# pandora_B_v1.net
KiCad netlist of a schematic drawn in EAGLE
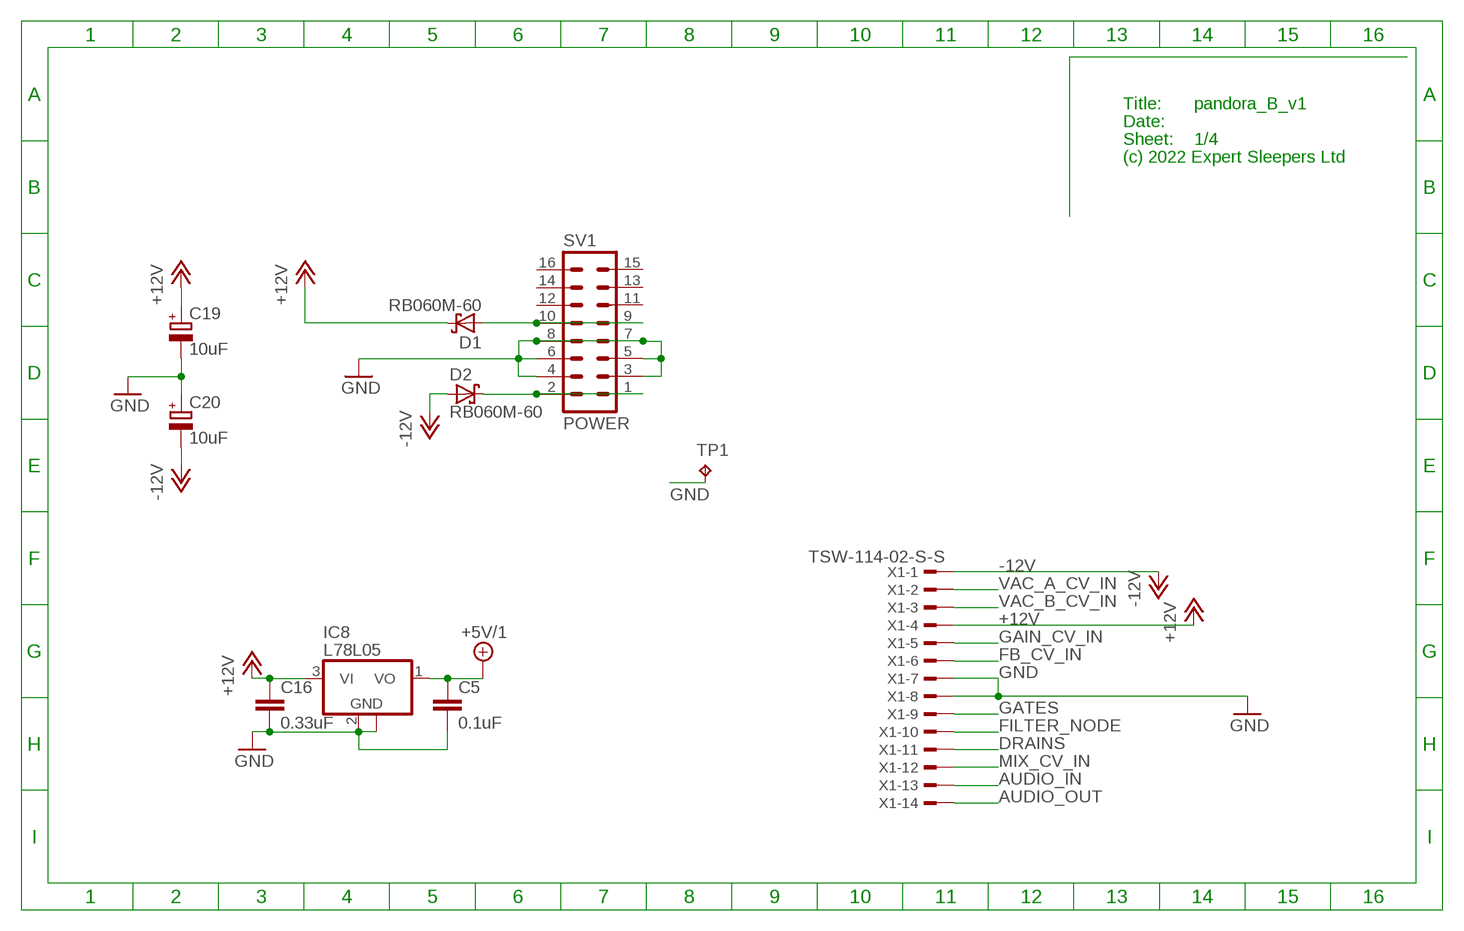
[diagram p0: schematic, sheet 1]
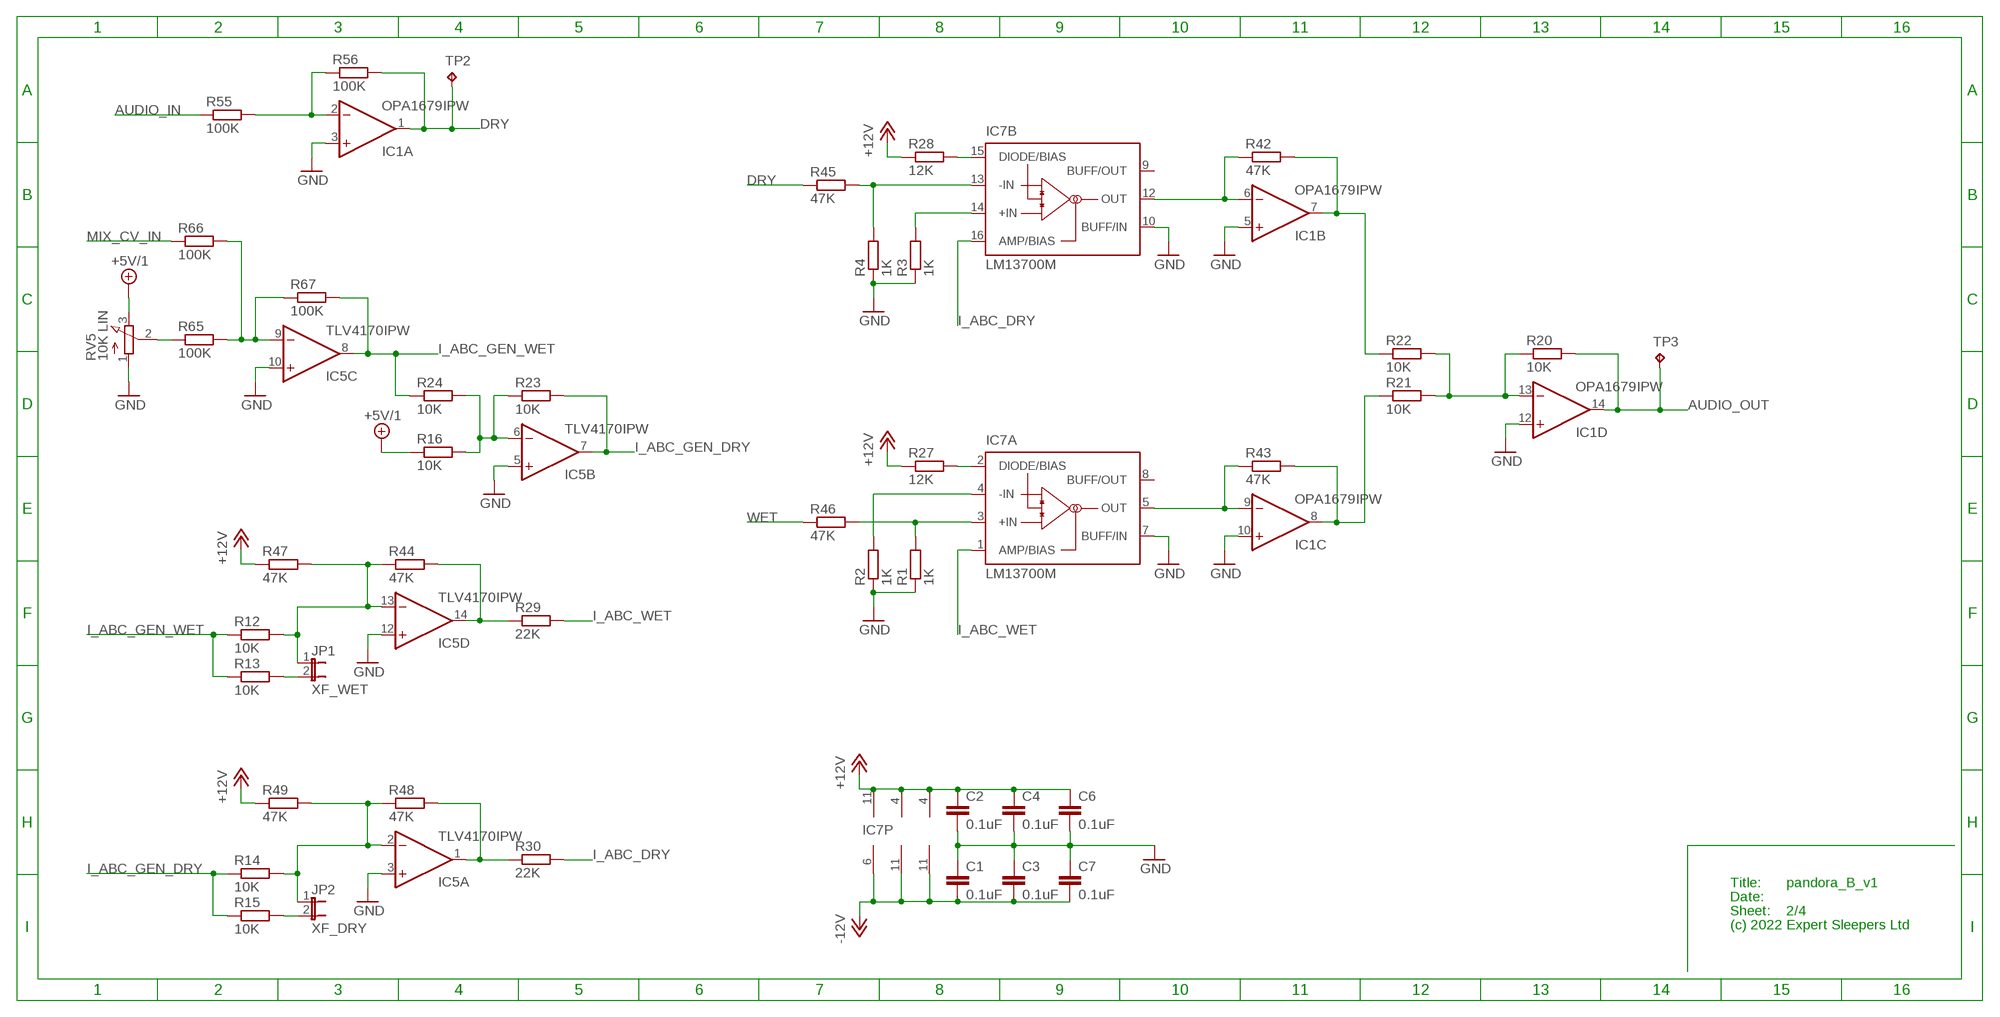
[diagram p1: schematic, sheet 2]
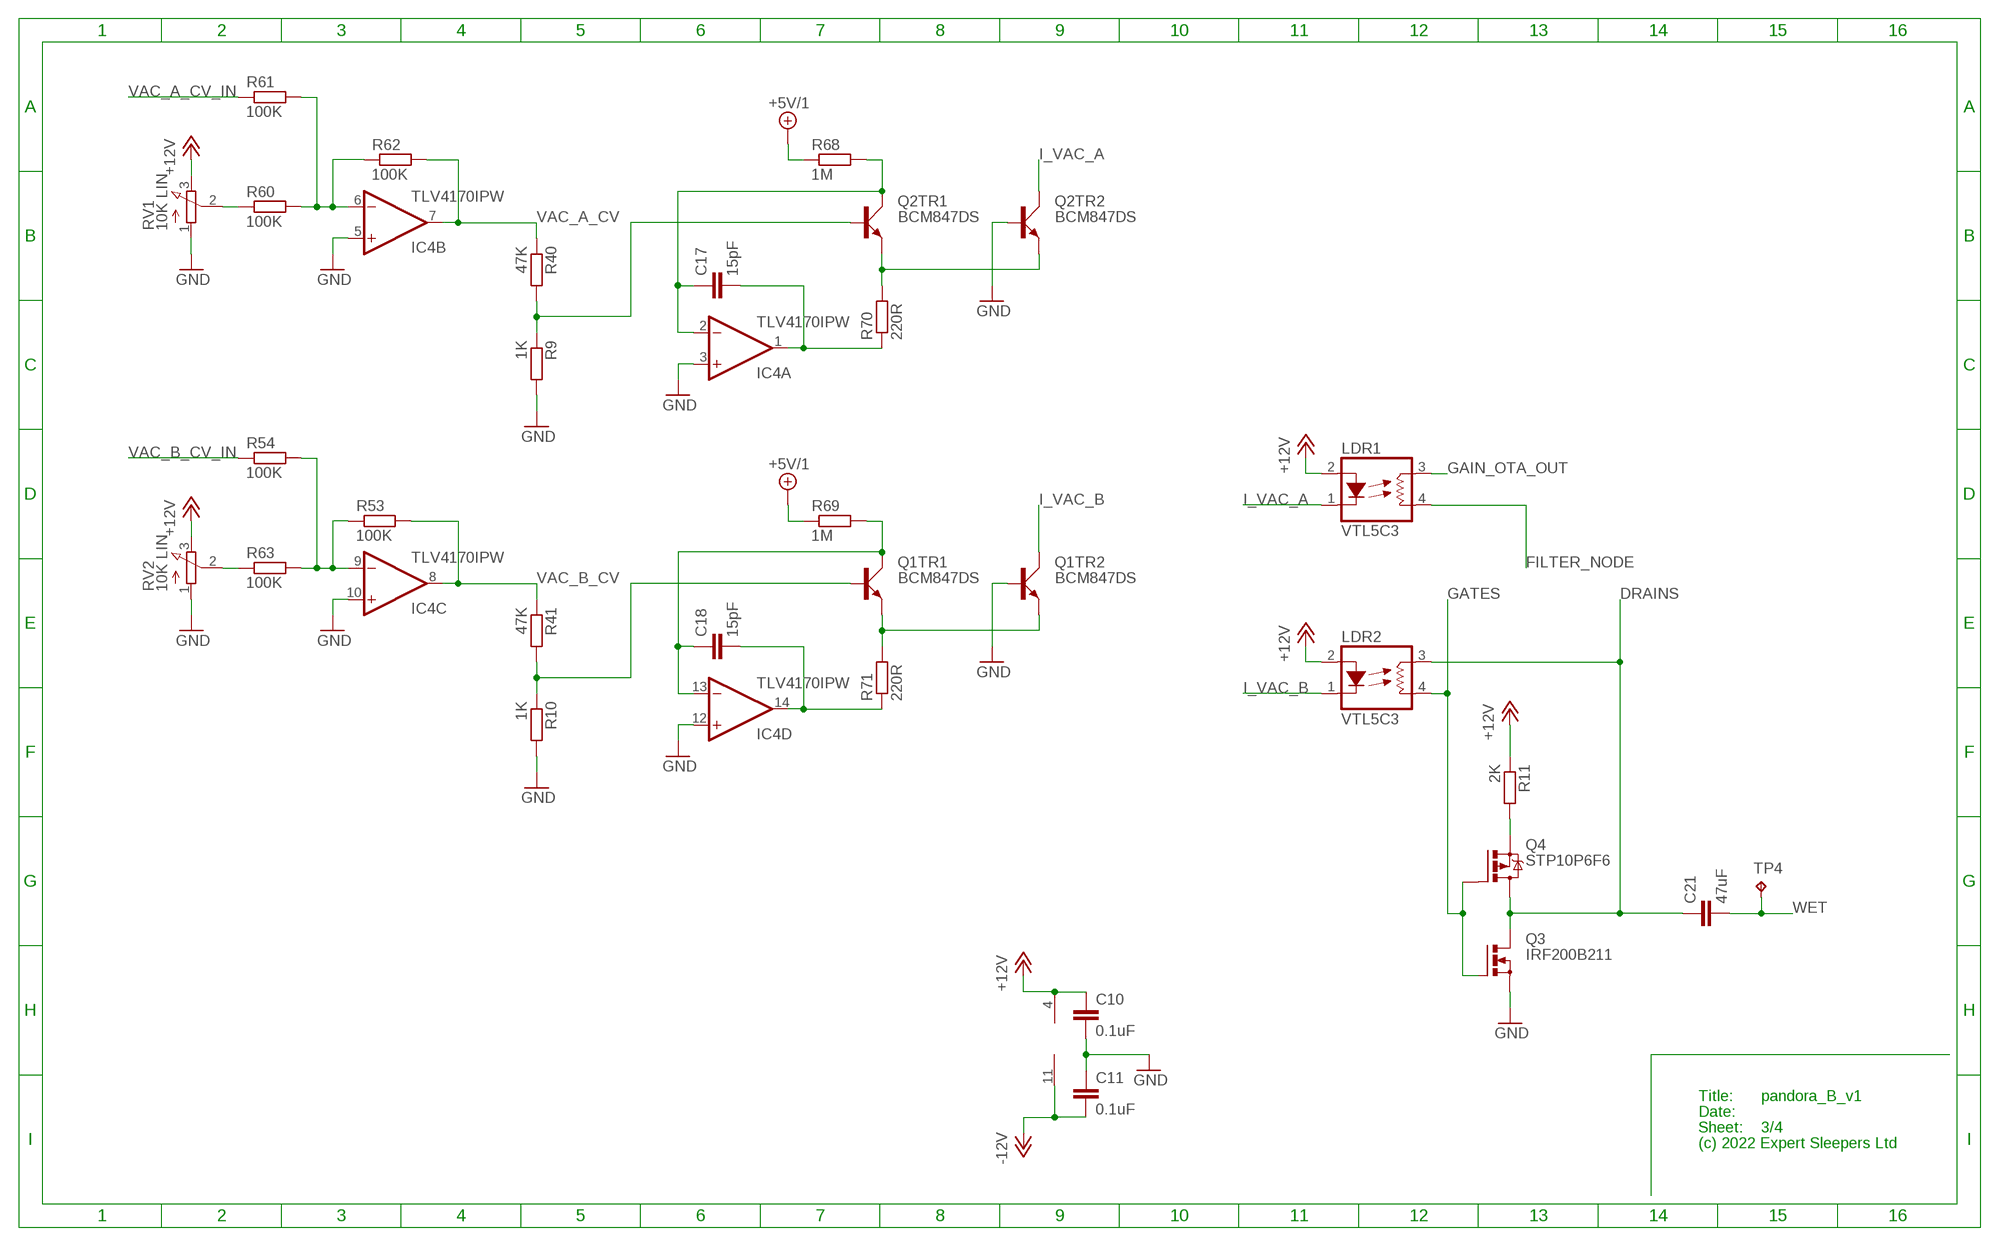
[diagram p2: schematic, sheet 3]
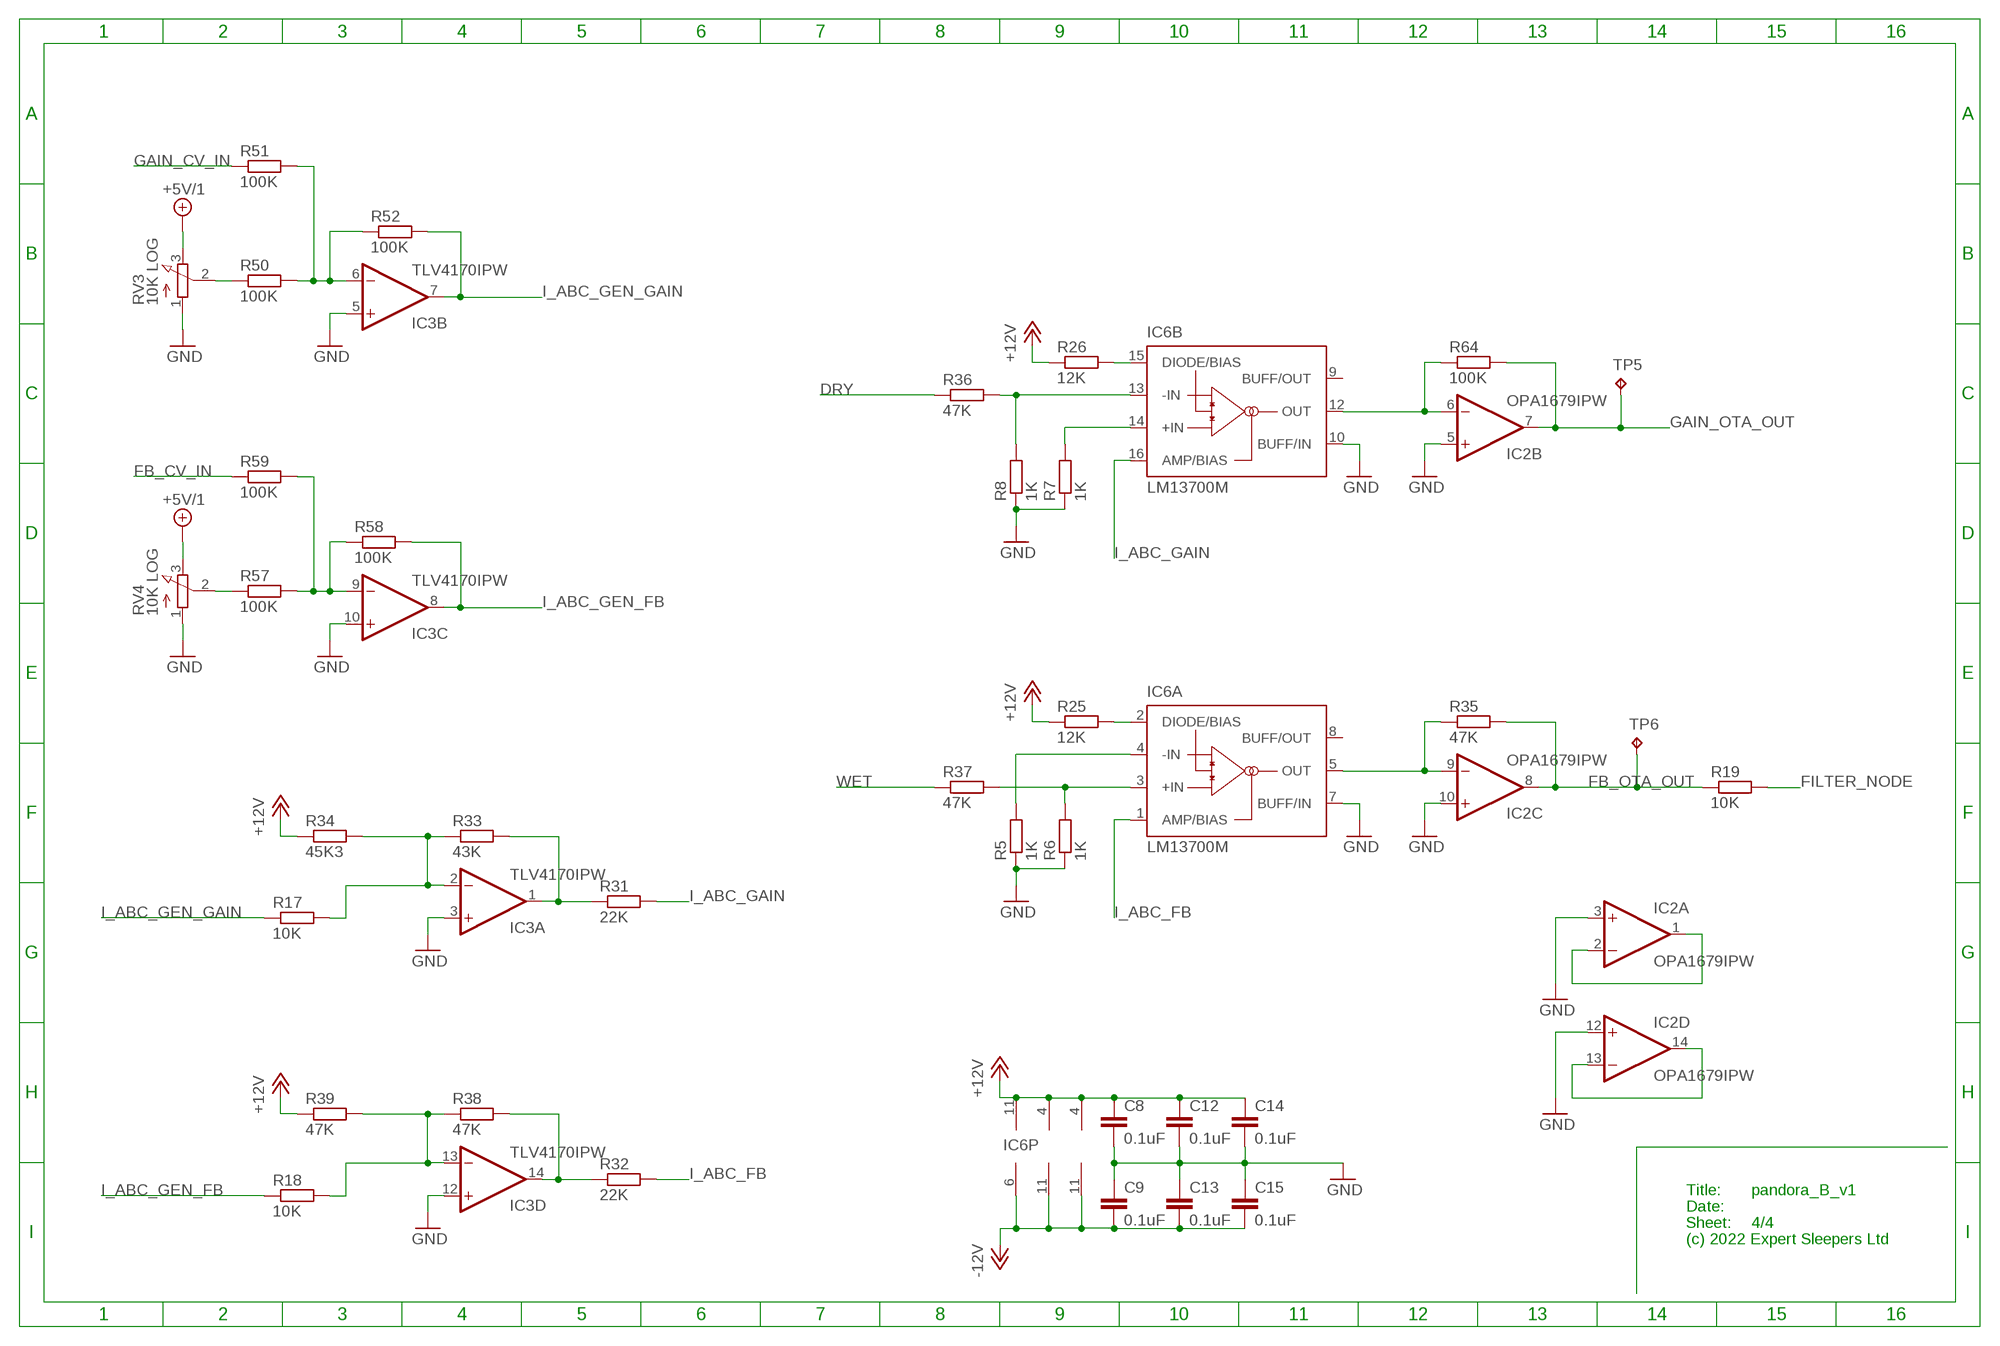
[diagram p3: schematic, sheet 4]

(export (version "E")
  (design (tool "Eeschema 10.0.6"))
  (components
    (comp (ref "C10")
      (value "0.1uF")
      (footprint "eagle-import:C0402")
      (libsource (lib "eagle-import") (part "C-EUC0402"))
    )
    (comp (ref "C11")
      (value "0.1uF")
      (footprint "eagle-import:C0402")
      (libsource (lib "eagle-import") (part "C-EUC0402"))
    )
    (comp (ref "C17")
      (value "15pF")
      (footprint "eagle-import:C0402")
      (libsource (lib "eagle-import") (part "C-EUC0402"))
    )
    (comp (ref "C18")
      (value "15pF")
      (footprint "eagle-import:C0402")
      (libsource (lib "eagle-import") (part "C-EUC0402"))
    )
    (comp (ref "C21")
      (value "47uF")
      (footprint "eagle-import:C1206")
      (libsource (lib "eagle-import") (part "C-EUC1206"))
    )
    (comp (ref "IC4")
      (value "TLV4170IPW")
      (footprint "eagle-import:PW_R-PDSO-G14")
      (libsource (lib "eagle-import") (part "TL074PW"))
    )
    (comp (ref "LDR1")
      (value "VTL5C3")
      (footprint "eagle-import:VTL5C")
      (fields (field (name "MF") "VACTEC PHOTO") (field (name "MPN") "VTL5C9"))
      (libsource (lib "eagle-import") (part "VTL5C9"))
    )
    (comp (ref "LDR2")
      (value "VTL5C3")
      (footprint "eagle-import:VTL5C")
      (fields (field (name "MF") "VACTEC PHOTO") (field (name "MPN") "VTL5C9"))
      (libsource (lib "eagle-import") (part "VTL5C9"))
    )
    (comp (ref "Q1")
      (value "BCM847DS")
      (footprint "eagle-import:SOT95P275X110-6N")
      (fields
        (field (name "ARROW_PART_NUMBER") "BCM847DS,135")
        (field (name "MOUSER_PART_NUMBER") "771-BCM847DS135")
      )
      (libsource (lib "eagle-import") (part "BCM847DS"))
    )
    (comp (ref "Q2")
      (value "BCM847DS")
      (footprint "eagle-import:SOT95P275X110-6N")
      (fields
        (field (name "ARROW_PART_NUMBER") "BCM847DS,135")
        (field (name "MOUSER_PART_NUMBER") "771-BCM847DS135")
      )
      (libsource (lib "eagle-import") (part "BCM847DS"))
    )
    (comp (ref "Q3")
      (value "IRF200B211")
      (footprint "eagle-import:TO220BV")
      (libsource (lib "eagle-import") (part "IRF512"))
    )
    (comp (ref "Q4")
      (value "STP10P6F6")
      (footprint "eagle-import:TO220BV")
      (libsource (lib "eagle-import") (part "IRF9530"))
    )
    (comp (ref "R9")
      (value "1K")
      (footprint "eagle-import:R0603")
      (libsource (lib "eagle-import") (part "R-EU_R0603"))
    )
    (comp (ref "R10")
      (value "1K")
      (footprint "eagle-import:R0603")
      (libsource (lib "eagle-import") (part "R-EU_R0603"))
    )
    (comp (ref "R11")
      (value "2K")
      (footprint "eagle-import:R1206")
      (libsource (lib "eagle-import") (part "R-EU_R1206"))
    )
    (comp (ref "R40")
      (value "47K")
      (footprint "eagle-import:R0603")
      (libsource (lib "eagle-import") (part "R-EU_R0603"))
    )
    (comp (ref "R41")
      (value "47K")
      (footprint "eagle-import:R0603")
      (libsource (lib "eagle-import") (part "R-EU_R0603"))
    )
    (comp (ref "R53")
      (value "100K")
      (footprint "eagle-import:R0603")
      (libsource (lib "eagle-import") (part "R-EU_R0603"))
    )
    (comp (ref "R54")
      (value "100K")
      (footprint "eagle-import:R0603")
      (libsource (lib "eagle-import") (part "R-EU_R0603"))
    )
    (comp (ref "R60")
      (value "100K")
      (footprint "eagle-import:R0603")
      (libsource (lib "eagle-import") (part "R-EU_R0603"))
    )
    (comp (ref "R61")
      (value "100K")
      (footprint "eagle-import:R0603")
      (libsource (lib "eagle-import") (part "R-EU_R0603"))
    )
    (comp (ref "R62")
      (value "100K")
      (footprint "eagle-import:R0603")
      (libsource (lib "eagle-import") (part "R-EU_R0603"))
    )
    (comp (ref "R63")
      (value "100K")
      (footprint "eagle-import:R0603")
      (libsource (lib "eagle-import") (part "R-EU_R0603"))
    )
    (comp (ref "R68")
      (value "1M")
      (footprint "eagle-import:R0603")
      (libsource (lib "eagle-import") (part "R-EU_R0603"))
    )
    (comp (ref "R69")
      (value "1M")
      (footprint "eagle-import:R0603")
      (libsource (lib "eagle-import") (part "R-EU_R0603"))
    )
    (comp (ref "R70")
      (value "220R")
      (footprint "eagle-import:R0805")
      (libsource (lib "eagle-import") (part "R-EU_R0805"))
    )
    (comp (ref "R71")
      (value "220R")
      (footprint "eagle-import:R0805")
      (libsource (lib "eagle-import") (part "R-EU_R0805"))
    )
    (comp (ref "RV1")
      (value "10K LIN")
      (footprint "eagle-import:RD1610NOA0X")
      (libsource (lib "eagle-import") (part "RD1610NOA0X"))
    )
    (comp (ref "RV2")
      (value "10K LIN")
      (footprint "eagle-import:RD1610NOA0X")
      (libsource (lib "eagle-import") (part "RD1610NOA0X"))
    )
    (comp (ref "TP4")
      (value "RA2")
      (footprint "eagle-import:P1-13")
      (libsource (lib "eagle-import") (part "TPPAD1-13"))
    )
    (comp (ref "C1")
      (value "0.1uF")
      (footprint "eagle-import:C0402")
      (libsource (lib "eagle-import") (part "C-EUC0402"))
    )
    (comp (ref "C2")
      (value "0.1uF")
      (footprint "eagle-import:C0402")
      (libsource (lib "eagle-import") (part "C-EUC0402"))
    )
    (comp (ref "C3")
      (value "0.1uF")
      (footprint "eagle-import:C0402")
      (libsource (lib "eagle-import") (part "C-EUC0402"))
    )
    (comp (ref "C4")
      (value "0.1uF")
      (footprint "eagle-import:C0402")
      (libsource (lib "eagle-import") (part "C-EUC0402"))
    )
    (comp (ref "C6")
      (value "0.1uF")
      (footprint "eagle-import:C0402")
      (libsource (lib "eagle-import") (part "C-EUC0402"))
    )
    (comp (ref "C7")
      (value "0.1uF")
      (footprint "eagle-import:C0402")
      (libsource (lib "eagle-import") (part "C-EUC0402"))
    )
    (comp (ref "IC1")
      (value "OPA1679IPW")
      (footprint "eagle-import:PW_R-PDSO-G14")
      (libsource (lib "eagle-import") (part "TL074PW"))
    )
    (comp (ref "IC5")
      (value "TLV4170IPW")
      (footprint "eagle-import:PW_R-PDSO-G14")
      (libsource (lib "eagle-import") (part "TL074PW"))
    )
    (comp (ref "IC7")
      (value "LM13700M")
      (footprint "eagle-import:SO16")
      (libsource (lib "eagle-import") (part "LM13700M"))
    )
    (comp (ref "JP1")
      (value "XF_WET")
      (footprint "eagle-import:JP1")
      (libsource (lib "eagle-import") (part "JP1E"))
    )
    (comp (ref "JP2")
      (value "XF_DRY")
      (footprint "eagle-import:JP1")
      (libsource (lib "eagle-import") (part "JP1E"))
    )
    (comp (ref "R1")
      (value "1K")
      (footprint "eagle-import:R0603")
      (libsource (lib "eagle-import") (part "R-EU_R0603"))
    )
    (comp (ref "R2")
      (value "1K")
      (footprint "eagle-import:R0603")
      (libsource (lib "eagle-import") (part "R-EU_R0603"))
    )
    (comp (ref "R3")
      (value "1K")
      (footprint "eagle-import:R0603")
      (libsource (lib "eagle-import") (part "R-EU_R0603"))
    )
    (comp (ref "R4")
      (value "1K")
      (footprint "eagle-import:R0603")
      (libsource (lib "eagle-import") (part "R-EU_R0603"))
    )
    (comp (ref "R12")
      (value "10K")
      (footprint "eagle-import:R0603")
      (libsource (lib "eagle-import") (part "R-EU_R0603"))
    )
    (comp (ref "R13")
      (value "10K")
      (footprint "eagle-import:R0603")
      (libsource (lib "eagle-import") (part "R-EU_R0603"))
    )
    (comp (ref "R14")
      (value "10K")
      (footprint "eagle-import:R0603")
      (libsource (lib "eagle-import") (part "R-EU_R0603"))
    )
    (comp (ref "R15")
      (value "10K")
      (footprint "eagle-import:R0603")
      (libsource (lib "eagle-import") (part "R-EU_R0603"))
    )
    (comp (ref "R16")
      (value "10K")
      (footprint "eagle-import:R0603")
      (libsource (lib "eagle-import") (part "R-EU_R0603"))
    )
    (comp (ref "R20")
      (value "10K")
      (footprint "eagle-import:R0603")
      (libsource (lib "eagle-import") (part "R-EU_R0603"))
    )
    (comp (ref "R21")
      (value "10K")
      (footprint "eagle-import:R0603")
      (libsource (lib "eagle-import") (part "R-EU_R0603"))
    )
    (comp (ref "R22")
      (value "10K")
      (footprint "eagle-import:R0603")
      (libsource (lib "eagle-import") (part "R-EU_R0603"))
    )
    (comp (ref "R23")
      (value "10K")
      (footprint "eagle-import:R0603")
      (libsource (lib "eagle-import") (part "R-EU_R0603"))
    )
    (comp (ref "R24")
      (value "10K")
      (footprint "eagle-import:R0603")
      (libsource (lib "eagle-import") (part "R-EU_R0603"))
    )
    (comp (ref "R27")
      (value "12K")
      (footprint "eagle-import:R0603")
      (libsource (lib "eagle-import") (part "R-EU_R0603"))
    )
    (comp (ref "R28")
      (value "12K")
      (footprint "eagle-import:R0603")
      (libsource (lib "eagle-import") (part "R-EU_R0603"))
    )
    (comp (ref "R29")
      (value "22K")
      (footprint "eagle-import:R0603")
      (libsource (lib "eagle-import") (part "R-EU_R0603"))
    )
    (comp (ref "R30")
      (value "22K")
      (footprint "eagle-import:R0603")
      (libsource (lib "eagle-import") (part "R-EU_R0603"))
    )
    (comp (ref "R42")
      (value "47K")
      (footprint "eagle-import:R0603")
      (libsource (lib "eagle-import") (part "R-EU_R0603"))
    )
    (comp (ref "R43")
      (value "47K")
      (footprint "eagle-import:R0603")
      (libsource (lib "eagle-import") (part "R-EU_R0603"))
    )
    (comp (ref "R44")
      (value "47K")
      (footprint "eagle-import:R0603")
      (libsource (lib "eagle-import") (part "R-EU_R0603"))
    )
    (comp (ref "R45")
      (value "47K")
      (footprint "eagle-import:R0603")
      (libsource (lib "eagle-import") (part "R-EU_R0603"))
    )
    (comp (ref "R46")
      (value "47K")
      (footprint "eagle-import:R0603")
      (libsource (lib "eagle-import") (part "R-EU_R0603"))
    )
    (comp (ref "R47")
      (value "47K")
      (footprint "eagle-import:R0603")
      (libsource (lib "eagle-import") (part "R-EU_R0603"))
    )
    (comp (ref "R48")
      (value "47K")
      (footprint "eagle-import:R0603")
      (libsource (lib "eagle-import") (part "R-EU_R0603"))
    )
    (comp (ref "R49")
      (value "47K")
      (footprint "eagle-import:R0603")
      (libsource (lib "eagle-import") (part "R-EU_R0603"))
    )
    (comp (ref "R55")
      (value "100K")
      (footprint "eagle-import:R0603")
      (libsource (lib "eagle-import") (part "R-EU_R0603"))
    )
    (comp (ref "R56")
      (value "100K")
      (footprint "eagle-import:R0603")
      (libsource (lib "eagle-import") (part "R-EU_R0603"))
    )
    (comp (ref "R65")
      (value "100K")
      (footprint "eagle-import:R0603")
      (libsource (lib "eagle-import") (part "R-EU_R0603"))
    )
    (comp (ref "R66")
      (value "100K")
      (footprint "eagle-import:R0603")
      (libsource (lib "eagle-import") (part "R-EU_R0603"))
    )
    (comp (ref "R67")
      (value "100K")
      (footprint "eagle-import:R0603")
      (libsource (lib "eagle-import") (part "R-EU_R0603"))
    )
    (comp (ref "RV5")
      (value "10K LIN")
      (footprint "eagle-import:RD1610NOA0X")
      (libsource (lib "eagle-import") (part "RD1610NOA0X"))
    )
    (comp (ref "TP2")
      (value "RA2")
      (footprint "eagle-import:P1-13")
      (libsource (lib "eagle-import") (part "TPPAD1-13"))
    )
    (comp (ref "TP3")
      (value "RA2")
      (footprint "eagle-import:P1-13")
      (libsource (lib "eagle-import") (part "TPPAD1-13"))
    )
    (comp (ref "C5")
      (value "0.1uF")
      (footprint "eagle-import:C0402")
      (libsource (lib "eagle-import") (part "C-EUC0402"))
    )
    (comp (ref "C16")
      (value "0.33uF")
      (footprint "eagle-import:C0805")
      (libsource (lib "eagle-import") (part "C-EUC0805"))
    )
    (comp (ref "C19")
      (value "10uF")
      (footprint "eagle-import:UD-4X5,8_NICHICON")
      (libsource (lib "eagle-import") (part "CPOL-EUUD-4X5,8"))
    )
    (comp (ref "C20")
      (value "10uF")
      (footprint "eagle-import:UD-4X5,8_NICHICON")
      (libsource (lib "eagle-import") (part "CPOL-EUUD-4X5,8"))
    )
    (comp (ref "D1")
      (value "RB060M-60")
      (footprint "eagle-import:SOD123FL")
      (libsource (lib "eagle-import") (part "RB060M-60"))
    )
    (comp (ref "D2")
      (value "RB060M-60")
      (footprint "eagle-import:SOD123FL")
      (libsource (lib "eagle-import") (part "RB060M-60"))
    )
    (comp (ref "IC8")
      (value "L78L05")
      (footprint "eagle-import:SOT89")
      (libsource (lib "eagle-import") (part "78LF05"))
    )
    (comp (ref "SV1")
      (value "POWER")
      (footprint "eagle-import:ML16")
      (libsource (lib "eagle-import") (part "ML16"))
    )
    (comp (ref "TP1")
      (value "RA2")
      (footprint "eagle-import:P1-13")
      (libsource (lib "eagle-import") (part "TPPAD1-13"))
    )
    (comp (ref "X1")
      (value "TSW-114-02-S-S")
      (footprint "eagle-import:TSW-114-02-S-S")
      (libsource (lib "eagle-import") (part "TSW-114-02-S-S"))
    )
    (comp (ref "C8")
      (value "0.1uF")
      (footprint "eagle-import:C0402")
      (libsource (lib "eagle-import") (part "C-EUC0402"))
    )
    (comp (ref "C9")
      (value "0.1uF")
      (footprint "eagle-import:C0402")
      (libsource (lib "eagle-import") (part "C-EUC0402"))
    )
    (comp (ref "C12")
      (value "0.1uF")
      (footprint "eagle-import:C0402")
      (libsource (lib "eagle-import") (part "C-EUC0402"))
    )
    (comp (ref "C13")
      (value "0.1uF")
      (footprint "eagle-import:C0402")
      (libsource (lib "eagle-import") (part "C-EUC0402"))
    )
    (comp (ref "C14")
      (value "0.1uF")
      (footprint "eagle-import:C0402")
      (libsource (lib "eagle-import") (part "C-EUC0402"))
    )
    (comp (ref "C15")
      (value "0.1uF")
      (footprint "eagle-import:C0402")
      (libsource (lib "eagle-import") (part "C-EUC0402"))
    )
    (comp (ref "IC2")
      (value "OPA1679IPW")
      (footprint "eagle-import:PW_R-PDSO-G14")
      (libsource (lib "eagle-import") (part "TL074PW"))
    )
    (comp (ref "IC3")
      (value "TLV4170IPW")
      (footprint "eagle-import:PW_R-PDSO-G14")
      (libsource (lib "eagle-import") (part "TL074PW"))
    )
    (comp (ref "IC6")
      (value "LM13700M")
      (footprint "eagle-import:SO16")
      (libsource (lib "eagle-import") (part "LM13700M"))
    )
    (comp (ref "R5")
      (value "1K")
      (footprint "eagle-import:R0603")
      (libsource (lib "eagle-import") (part "R-EU_R0603"))
    )
    (comp (ref "R6")
      (value "1K")
      (footprint "eagle-import:R0603")
      (libsource (lib "eagle-import") (part "R-EU_R0603"))
    )
    (comp (ref "R7")
      (value "1K")
      (footprint "eagle-import:R0603")
      (libsource (lib "eagle-import") (part "R-EU_R0603"))
    )
    (comp (ref "R8")
      (value "1K")
      (footprint "eagle-import:R0603")
      (libsource (lib "eagle-import") (part "R-EU_R0603"))
    )
    (comp (ref "R17")
      (value "10K")
      (footprint "eagle-import:R0603")
      (libsource (lib "eagle-import") (part "R-EU_R0603"))
    )
    (comp (ref "R18")
      (value "10K")
      (footprint "eagle-import:R0603")
      (libsource (lib "eagle-import") (part "R-EU_R0603"))
    )
    (comp (ref "R19")
      (value "10K")
      (footprint "eagle-import:R0603")
      (libsource (lib "eagle-import") (part "R-EU_R0603"))
    )
    (comp (ref "R25")
      (value "12K")
      (footprint "eagle-import:R0603")
      (libsource (lib "eagle-import") (part "R-EU_R0603"))
    )
    (comp (ref "R26")
      (value "12K")
      (footprint "eagle-import:R0603")
      (libsource (lib "eagle-import") (part "R-EU_R0603"))
    )
    (comp (ref "R31")
      (value "22K")
      (footprint "eagle-import:R0603")
      (libsource (lib "eagle-import") (part "R-EU_R0603"))
    )
    (comp (ref "R32")
      (value "22K")
      (footprint "eagle-import:R0603")
      (libsource (lib "eagle-import") (part "R-EU_R0603"))
    )
    (comp (ref "R33")
      (value "43K")
      (footprint "eagle-import:R0603")
      (libsource (lib "eagle-import") (part "R-EU_R0603"))
    )
    (comp (ref "R34")
      (value "45K3")
      (footprint "eagle-import:R0603")
      (libsource (lib "eagle-import") (part "R-EU_R0603"))
    )
    (comp (ref "R35")
      (value "47K")
      (footprint "eagle-import:R0603")
      (libsource (lib "eagle-import") (part "R-EU_R0603"))
    )
    (comp (ref "R36")
      (value "47K")
      (footprint "eagle-import:R0603")
      (libsource (lib "eagle-import") (part "R-EU_R0603"))
    )
    (comp (ref "R37")
      (value "47K")
      (footprint "eagle-import:R0603")
      (libsource (lib "eagle-import") (part "R-EU_R0603"))
    )
    (comp (ref "R38")
      (value "47K")
      (footprint "eagle-import:R0603")
      (libsource (lib "eagle-import") (part "R-EU_R0603"))
    )
    (comp (ref "R39")
      (value "47K")
      (footprint "eagle-import:R0603")
      (libsource (lib "eagle-import") (part "R-EU_R0603"))
    )
    (comp (ref "R50")
      (value "100K")
      (footprint "eagle-import:R0603")
      (libsource (lib "eagle-import") (part "R-EU_R0603"))
    )
    (comp (ref "R51")
      (value "100K")
      (footprint "eagle-import:R0603")
      (libsource (lib "eagle-import") (part "R-EU_R0603"))
    )
    (comp (ref "R52")
      (value "100K")
      (footprint "eagle-import:R0603")
      (libsource (lib "eagle-import") (part "R-EU_R0603"))
    )
    (comp (ref "R57")
      (value "100K")
      (footprint "eagle-import:R0603")
      (libsource (lib "eagle-import") (part "R-EU_R0603"))
    )
    (comp (ref "R58")
      (value "100K")
      (footprint "eagle-import:R0603")
      (libsource (lib "eagle-import") (part "R-EU_R0603"))
    )
    (comp (ref "R59")
      (value "100K")
      (footprint "eagle-import:R0603")
      (libsource (lib "eagle-import") (part "R-EU_R0603"))
    )
    (comp (ref "R64")
      (value "100K")
      (footprint "eagle-import:R0603")
      (libsource (lib "eagle-import") (part "R-EU_R0603"))
    )
    (comp (ref "RV3")
      (value "10K LOG")
      (footprint "eagle-import:RD1610NOA0X")
      (libsource (lib "eagle-import") (part "RD1610NOA0X"))
    )
    (comp (ref "RV4")
      (value "10K LOG")
      (footprint "eagle-import:RD1610NOA0X")
      (libsource (lib "eagle-import") (part "RD1610NOA0X"))
    )
    (comp (ref "TP5")
      (value "RA2")
      (footprint "eagle-import:P1-13")
      (libsource (lib "eagle-import") (part "TPPAD1-13"))
    )
    (comp (ref "TP6")
      (value "RA2")
      (footprint "eagle-import:P1-13")
      (libsource (lib "eagle-import") (part "TPPAD1-13"))
    )
  )
  (nets
    (net (code "1") (name "+5V{slash}1") (class "Default")
      (node (ref "C5") (pin "1") (pinfunction "1_1") (pintype "passive"))
      (node (ref "IC8") (pin "1") (pinfunction "VO_1") (pintype "passive"))
      (node (ref "R16") (pin "1") (pinfunction "1_1") (pintype "passive"))
      (node (ref "R68") (pin "1") (pinfunction "1_1") (pintype "passive"))
      (node (ref "R69") (pin "1") (pinfunction "1_1") (pintype "passive"))
      (node (ref "RV3") (pin "3") (pinfunction "E_3") (pintype "passive"))
      (node (ref "RV4") (pin "3") (pinfunction "E_3") (pintype "passive"))
      (node (ref "RV5") (pin "3") (pinfunction "E_3") (pintype "passive"))
    )
    (net (code "2") (name "+12V") (class "Default")
      (node (ref "C10") (pin "1") (pinfunction "1_1") (pintype "passive"))
      (node (ref "C12") (pin "1") (pinfunction "1_1") (pintype "passive"))
      (node (ref "C14") (pin "1") (pinfunction "1_1") (pintype "passive"))
      (node (ref "C16") (pin "1") (pinfunction "1_1") (pintype "passive"))
      (node (ref "C19") (pin "+") (pinfunction "+_+") (pintype "passive"))
      (node (ref "C2") (pin "1") (pinfunction "1_1") (pintype "passive"))
      (node (ref "C4") (pin "1") (pinfunction "1_1") (pintype "passive"))
      (node (ref "C6") (pin "1") (pinfunction "1_1") (pintype "passive"))
      (node (ref "C8") (pin "1") (pinfunction "1_1") (pintype "passive"))
      (node (ref "D1") (pin "C") (pinfunction "C_C") (pintype "passive"))
      (node (ref "IC1") (pin "4") (pinfunction "V+_4") (pintype "power_in"))
      (node (ref "IC2") (pin "4") (pinfunction "V+_4") (pintype "power_in"))
      (node (ref "IC3") (pin "4") (pinfunction "V+_4") (pintype "power_in"))
      (node (ref "IC4") (pin "4") (pinfunction "V+_4") (pintype "power_in"))
      (node (ref "IC5") (pin "4") (pinfunction "V+_4") (pintype "power_in"))
      (node (ref "IC6") (pin "11") (pinfunction "V+_11") (pintype "power_in"))
      (node (ref "IC7") (pin "11") (pinfunction "V+_11") (pintype "power_in"))
      (node (ref "IC8") (pin "3") (pinfunction "VI_3") (pintype "input"))
      (node (ref "LDR1") (pin "2") (pinfunction "A_2") (pintype "passive"))
      (node (ref "LDR2") (pin "2") (pinfunction "A_2") (pintype "passive"))
      (node (ref "R11") (pin "1") (pinfunction "1_1") (pintype "passive"))
      (node (ref "R25") (pin "1") (pinfunction "1_1") (pintype "passive"))
      (node (ref "R26") (pin "1") (pinfunction "1_1") (pintype "passive"))
      (node (ref "R27") (pin "1") (pinfunction "1_1") (pintype "passive"))
      (node (ref "R28") (pin "1") (pinfunction "1_1") (pintype "passive"))
      (node (ref "R34") (pin "1") (pinfunction "1_1") (pintype "passive"))
      (node (ref "R39") (pin "1") (pinfunction "1_1") (pintype "passive"))
      (node (ref "R47") (pin "1") (pinfunction "1_1") (pintype "passive"))
      (node (ref "R49") (pin "1") (pinfunction "1_1") (pintype "passive"))
      (node (ref "RV1") (pin "3") (pinfunction "E_3") (pintype "passive"))
      (node (ref "RV2") (pin "3") (pinfunction "E_3") (pintype "passive"))
      (node (ref "X1") (pin "4") (pinfunction "1_4") (pintype "passive"))
    )
    (net (code "3") (name "-12V") (class "Default")
      (node (ref "C1") (pin "2") (pinfunction "2_2") (pintype "passive"))
      (node (ref "C11") (pin "2") (pinfunction "2_2") (pintype "passive"))
      (node (ref "C13") (pin "2") (pinfunction "2_2") (pintype "passive"))
      (node (ref "C15") (pin "2") (pinfunction "2_2") (pintype "passive"))
      (node (ref "C20") (pin "-") (pinfunction "-_-") (pintype "passive"))
      (node (ref "C3") (pin "2") (pinfunction "2_2") (pintype "passive"))
      (node (ref "C7") (pin "2") (pinfunction "2_2") (pintype "passive"))
      (node (ref "C9") (pin "2") (pinfunction "2_2") (pintype "passive"))
      (node (ref "D2") (pin "A") (pinfunction "A_A") (pintype "passive"))
      (node (ref "IC1") (pin "11") (pinfunction "V-_11") (pintype "power_in"))
      (node (ref "IC2") (pin "11") (pinfunction "V-_11") (pintype "power_in"))
      (node (ref "IC3") (pin "11") (pinfunction "V-_11") (pintype "power_in"))
      (node (ref "IC4") (pin "11") (pinfunction "V-_11") (pintype "power_in"))
      (node (ref "IC5") (pin "11") (pinfunction "V-_11") (pintype "power_in"))
      (node (ref "IC6") (pin "6") (pinfunction "V-_6") (pintype "power_in"))
      (node (ref "IC7") (pin "6") (pinfunction "V-_6") (pintype "power_in"))
      (node (ref "X1") (pin "1") (pinfunction "1_1") (pintype "passive"))
    )
    (net (code "4") (name "AUDIO_IN") (class "Default")
      (node (ref "R55") (pin "1") (pinfunction "1_1") (pintype "passive"))
      (node (ref "X1") (pin "13") (pinfunction "1_13") (pintype "passive"))
    )
    (net (code "5") (name "AUDIO_OUT") (class "Default")
      (node (ref "IC1") (pin "14") (pinfunction "OUT_14") (pintype "output"))
      (node (ref "R20") (pin "2") (pinfunction "2_2") (pintype "passive"))
      (node (ref "TP3") (pin "TP") (pinfunction "TP_TP") (pintype "input"))
      (node (ref "X1") (pin "14") (pinfunction "1_14") (pintype "passive"))
    )
    (net (code "6") (name "DRAINS") (class "Default")
      (node (ref "C21") (pin "1") (pinfunction "1_1") (pintype "passive"))
      (node (ref "LDR2") (pin "3") (pinfunction "L1_3") (pintype "passive"))
      (node (ref "Q3") (pin "D") (pinfunction "D_D") (pintype "passive"))
      (node (ref "Q4") (pin "D") (pinfunction "D_D") (pintype "passive"))
      (node (ref "X1") (pin "11") (pinfunction "1_11") (pintype "passive"))
    )
    (net (code "7") (name "DRY") (class "Default")
      (node (ref "IC1") (pin "1") (pinfunction "OUT_1") (pintype "output"))
      (node (ref "R36") (pin "1") (pinfunction "1_1") (pintype "passive"))
      (node (ref "R45") (pin "1") (pinfunction "1_1") (pintype "passive"))
      (node (ref "R56") (pin "2") (pinfunction "2_2") (pintype "passive"))
      (node (ref "TP2") (pin "TP") (pinfunction "TP_TP") (pintype "input"))
    )
    (net (code "8") (name "FB_CV_IN") (class "Default")
      (node (ref "R59") (pin "1") (pinfunction "1_1") (pintype "passive"))
      (node (ref "X1") (pin "6") (pinfunction "1_6") (pintype "passive"))
    )
    (net (code "9") (name "FB_OTA_OUT") (class "Default")
      (node (ref "IC2") (pin "8") (pinfunction "OUT_8") (pintype "output"))
      (node (ref "R19") (pin "1") (pinfunction "1_1") (pintype "passive"))
      (node (ref "R35") (pin "2") (pinfunction "2_2") (pintype "passive"))
      (node (ref "TP6") (pin "TP") (pinfunction "TP_TP") (pintype "input"))
    )
    (net (code "10") (name "FILTER_NODE") (class "Default")
      (node (ref "LDR1") (pin "4") (pinfunction "L2_4") (pintype "passive"))
      (node (ref "R19") (pin "2") (pinfunction "2_2") (pintype "passive"))
      (node (ref "X1") (pin "10") (pinfunction "1_10") (pintype "passive"))
    )
    (net (code "11") (name "GAIN_CV_IN") (class "Default")
      (node (ref "R51") (pin "1") (pinfunction "1_1") (pintype "passive"))
      (node (ref "X1") (pin "5") (pinfunction "1_5") (pintype "passive"))
    )
    (net (code "12") (name "GAIN_OTA_OUT") (class "Default")
      (node (ref "IC2") (pin "7") (pinfunction "OUT_7") (pintype "output"))
      (node (ref "LDR1") (pin "3") (pinfunction "L1_3") (pintype "passive"))
      (node (ref "R64") (pin "2") (pinfunction "2_2") (pintype "passive"))
      (node (ref "TP5") (pin "TP") (pinfunction "TP_TP") (pintype "input"))
    )
    (net (code "13") (name "GATES") (class "Default")
      (node (ref "LDR2") (pin "4") (pinfunction "L2_4") (pintype "passive"))
      (node (ref "Q3") (pin "G") (pinfunction "G_G") (pintype "passive"))
      (node (ref "Q4") (pin "G") (pinfunction "G_G") (pintype "passive"))
      (node (ref "X1") (pin "9") (pinfunction "1_9") (pintype "passive"))
    )
    (net (code "14") (name "GND") (class "Default")
      (node (ref "C1") (pin "1") (pinfunction "1_1") (pintype "passive"))
      (node (ref "C10") (pin "2") (pinfunction "2_2") (pintype "passive"))
      (node (ref "C11") (pin "1") (pinfunction "1_1") (pintype "passive"))
      (node (ref "C12") (pin "2") (pinfunction "2_2") (pintype "passive"))
      (node (ref "C13") (pin "1") (pinfunction "1_1") (pintype "passive"))
      (node (ref "C14") (pin "2") (pinfunction "2_2") (pintype "passive"))
      (node (ref "C15") (pin "1") (pinfunction "1_1") (pintype "passive"))
      (node (ref "C16") (pin "2") (pinfunction "2_2") (pintype "passive"))
      (node (ref "C19") (pin "-") (pinfunction "-_-") (pintype "passive"))
      (node (ref "C2") (pin "2") (pinfunction "2_2") (pintype "passive"))
      (node (ref "C20") (pin "+") (pinfunction "+_+") (pintype "passive"))
      (node (ref "C3") (pin "1") (pinfunction "1_1") (pintype "passive"))
      (node (ref "C4") (pin "2") (pinfunction "2_2") (pintype "passive"))
      (node (ref "C5") (pin "2") (pinfunction "2_2") (pintype "passive"))
      (node (ref "C6") (pin "2") (pinfunction "2_2") (pintype "passive"))
      (node (ref "C7") (pin "1") (pinfunction "1_1") (pintype "passive"))
      (node (ref "C8") (pin "2") (pinfunction "2_2") (pintype "passive"))
      (node (ref "C9") (pin "1") (pinfunction "1_1") (pintype "passive"))
      (node (ref "IC1") (pin "10") (pinfunction "+IN_10") (pintype "input"))
      (node (ref "IC1") (pin "12") (pinfunction "+IN_12") (pintype "input"))
      (node (ref "IC1") (pin "3") (pinfunction "+IN_3") (pintype "input"))
      (node (ref "IC1") (pin "5") (pinfunction "+IN_5") (pintype "input"))
      (node (ref "IC2") (pin "10") (pinfunction "+IN_10") (pintype "input"))
      (node (ref "IC2") (pin "12") (pinfunction "+IN_12") (pintype "input"))
      (node (ref "IC2") (pin "3") (pinfunction "+IN_3") (pintype "input"))
      (node (ref "IC2") (pin "5") (pinfunction "+IN_5") (pintype "input"))
      (node (ref "IC3") (pin "10") (pinfunction "+IN_10") (pintype "input"))
      (node (ref "IC3") (pin "12") (pinfunction "+IN_12") (pintype "input"))
      (node (ref "IC3") (pin "3") (pinfunction "+IN_3") (pintype "input"))
      (node (ref "IC3") (pin "5") (pinfunction "+IN_5") (pintype "input"))
      (node (ref "IC4") (pin "10") (pinfunction "+IN_10") (pintype "input"))
      (node (ref "IC4") (pin "12") (pinfunction "+IN_12") (pintype "input"))
      (node (ref "IC4") (pin "3") (pinfunction "+IN_3") (pintype "input"))
      (node (ref "IC4") (pin "5") (pinfunction "+IN_5") (pintype "input"))
      (node (ref "IC5") (pin "10") (pinfunction "+IN_10") (pintype "input"))
      (node (ref "IC5") (pin "12") (pinfunction "+IN_12") (pintype "input"))
      (node (ref "IC5") (pin "3") (pinfunction "+IN_3") (pintype "input"))
      (node (ref "IC5") (pin "5") (pinfunction "+IN_5") (pintype "input"))
      (node (ref "IC6") (pin "10") (pinfunction "BUFF/IN_10") (pintype "input"))
      (node (ref "IC6") (pin "7") (pinfunction "BUFF/IN_7") (pintype "input"))
      (node (ref "IC7") (pin "10") (pinfunction "BUFF/IN_10") (pintype "input"))
      (node (ref "IC7") (pin "7") (pinfunction "BUFF/IN_7") (pintype "input"))
      (node (ref "IC8") (pin "2") (pinfunction "GND_2") (pintype "passive"))
      (node (ref "IC8") (pin "2@1") (pinfunction "GND_2@1") (pintype "passive"))
      (node (ref "Q1") (pin "5") (pinfunction "B_5") (pintype "passive"))
      (node (ref "Q2") (pin "5") (pinfunction "B_5") (pintype "passive"))
      (node (ref "Q3") (pin "S") (pinfunction "S_S") (pintype "passive"))
      (node (ref "R1") (pin "1") (pinfunction "1_1") (pintype "passive"))
      (node (ref "R10") (pin "2") (pinfunction "2_2") (pintype "passive"))
      (node (ref "R2") (pin "1") (pinfunction "1_1") (pintype "passive"))
      (node (ref "R3") (pin "1") (pinfunction "1_1") (pintype "passive"))
      (node (ref "R4") (pin "1") (pinfunction "1_1") (pintype "passive"))
      (node (ref "R5") (pin "1") (pinfunction "1_1") (pintype "passive"))
      (node (ref "R6") (pin "1") (pinfunction "1_1") (pintype "passive"))
      (node (ref "R7") (pin "1") (pinfunction "1_1") (pintype "passive"))
      (node (ref "R8") (pin "1") (pinfunction "1_1") (pintype "passive"))
      (node (ref "R9") (pin "2") (pinfunction "2_2") (pintype "passive"))
      (node (ref "RV1") (pin "1") (pinfunction "A_1") (pintype "passive"))
      (node (ref "RV2") (pin "1") (pinfunction "A_1") (pintype "passive"))
      (node (ref "RV3") (pin "1") (pinfunction "A_1") (pintype "passive"))
      (node (ref "RV4") (pin "1") (pinfunction "A_1") (pintype "passive"))
      (node (ref "RV5") (pin "1") (pinfunction "A_1") (pintype "passive"))
      (node (ref "SV1") (pin "3") (pinfunction "3_3") (pintype "passive"))
      (node (ref "SV1") (pin "4") (pinfunction "4_4") (pintype "passive"))
      (node (ref "SV1") (pin "5") (pinfunction "5_5") (pintype "passive"))
      (node (ref "SV1") (pin "6") (pinfunction "6_6") (pintype "passive"))
      (node (ref "SV1") (pin "7") (pinfunction "7_7") (pintype "passive"))
      (node (ref "SV1") (pin "8") (pinfunction "8_8") (pintype "passive"))
      (node (ref "TP1") (pin "TP") (pinfunction "TP_TP") (pintype "input"))
      (node (ref "X1") (pin "7") (pinfunction "1_7") (pintype "passive"))
      (node (ref "X1") (pin "8") (pinfunction "1_8") (pintype "passive"))
    )
    (net (code "15") (name "I_ABC_DRY") (class "Default")
      (node (ref "IC7") (pin "16") (pinfunction "AMP/BIAS_16") (pintype "passive"))
      (node (ref "R30") (pin "2") (pinfunction "2_2") (pintype "passive"))
    )
    (net (code "16") (name "I_ABC_FB") (class "Default")
      (node (ref "IC6") (pin "1") (pinfunction "AMP/BIAS_1") (pintype "passive"))
      (node (ref "R32") (pin "2") (pinfunction "2_2") (pintype "passive"))
    )
    (net (code "17") (name "I_ABC_GAIN") (class "Default")
      (node (ref "IC6") (pin "16") (pinfunction "AMP/BIAS_16") (pintype "passive"))
      (node (ref "R31") (pin "2") (pinfunction "2_2") (pintype "passive"))
    )
    (net (code "18") (name "I_ABC_GEN_DRY") (class "Default")
      (node (ref "IC5") (pin "7") (pinfunction "OUT_7") (pintype "output"))
      (node (ref "R14") (pin "1") (pinfunction "1_1") (pintype "passive"))
      (node (ref "R15") (pin "1") (pinfunction "1_1") (pintype "passive"))
      (node (ref "R23") (pin "2") (pinfunction "2_2") (pintype "passive"))
    )
    (net (code "19") (name "I_ABC_GEN_FB") (class "Default")
      (node (ref "IC3") (pin "8") (pinfunction "OUT_8") (pintype "output"))
      (node (ref "R18") (pin "1") (pinfunction "1_1") (pintype "passive"))
      (node (ref "R58") (pin "2") (pinfunction "2_2") (pintype "passive"))
    )
    (net (code "20") (name "I_ABC_GEN_GAIN") (class "Default")
      (node (ref "IC3") (pin "7") (pinfunction "OUT_7") (pintype "output"))
      (node (ref "R17") (pin "1") (pinfunction "1_1") (pintype "passive"))
      (node (ref "R52") (pin "2") (pinfunction "2_2") (pintype "passive"))
    )
    (net (code "21") (name "I_ABC_GEN_WET") (class "Default")
      (node (ref "IC5") (pin "8") (pinfunction "OUT_8") (pintype "output"))
      (node (ref "R12") (pin "1") (pinfunction "1_1") (pintype "passive"))
      (node (ref "R13") (pin "1") (pinfunction "1_1") (pintype "passive"))
      (node (ref "R24") (pin "1") (pinfunction "1_1") (pintype "passive"))
      (node (ref "R67") (pin "2") (pinfunction "2_2") (pintype "passive"))
    )
    (net (code "22") (name "I_ABC_WET") (class "Default")
      (node (ref "IC7") (pin "1") (pinfunction "AMP/BIAS_1") (pintype "passive"))
      (node (ref "R29") (pin "2") (pinfunction "2_2") (pintype "passive"))
    )
    (net (code "23") (name "I_VAC_A") (class "Default")
      (node (ref "LDR1") (pin "1") (pinfunction "C_1") (pintype "passive"))
      (node (ref "Q2") (pin "3") (pinfunction "C_3") (pintype "passive"))
    )
    (net (code "24") (name "I_VAC_B") (class "Default")
      (node (ref "LDR2") (pin "1") (pinfunction "C_1") (pintype "passive"))
      (node (ref "Q1") (pin "3") (pinfunction "C_3") (pintype "passive"))
    )
    (net (code "25") (name "MIX_CV_IN") (class "Default")
      (node (ref "R66") (pin "1") (pinfunction "1_1") (pintype "passive"))
      (node (ref "X1") (pin "12") (pinfunction "1_12") (pintype "passive"))
    )
    (net (code "26") (name "Net-(D1-PadA)") (class "Default")
      (node (ref "D1") (pin "A") (pinfunction "A_A") (pintype "passive"))
      (node (ref "SV1") (pin "10") (pinfunction "10_10") (pintype "passive"))
      (node (ref "SV1") (pin "9") (pinfunction "9_9") (pintype "passive"))
    )
    (net (code "27") (name "Net-(D2-PadC)") (class "Default")
      (node (ref "D2") (pin "C") (pinfunction "C_C") (pintype "passive"))
      (node (ref "SV1") (pin "1") (pinfunction "1_1") (pintype "passive"))
      (node (ref "SV1") (pin "2") (pinfunction "2_2") (pintype "passive"))
    )
    (net (code "28") (name "Net-(IC1A--IN)") (class "Default")
      (node (ref "IC1") (pin "2") (pinfunction "-IN_2") (pintype "input"))
      (node (ref "R55") (pin "2") (pinfunction "2_2") (pintype "passive"))
      (node (ref "R56") (pin "1") (pinfunction "1_1") (pintype "passive"))
    )
    (net (code "29") (name "Net-(IC1B--IN)") (class "Default")
      (node (ref "IC1") (pin "6") (pinfunction "-IN_6") (pintype "input"))
      (node (ref "IC7") (pin "12") (pinfunction "OUT_12") (pintype "output"))
      (node (ref "R42") (pin "1") (pinfunction "1_1") (pintype "passive"))
    )
    (net (code "30") (name "Net-(IC1B-OUT)") (class "Default")
      (node (ref "IC1") (pin "7") (pinfunction "OUT_7") (pintype "output"))
      (node (ref "R22") (pin "1") (pinfunction "1_1") (pintype "passive"))
      (node (ref "R42") (pin "2") (pinfunction "2_2") (pintype "passive"))
    )
    (net (code "31") (name "Net-(IC1C--IN)") (class "Default")
      (node (ref "IC1") (pin "9") (pinfunction "-IN_9") (pintype "input"))
      (node (ref "IC7") (pin "5") (pinfunction "OUT_5") (pintype "output"))
      (node (ref "R43") (pin "1") (pinfunction "1_1") (pintype "passive"))
    )
    (net (code "32") (name "Net-(IC1C-OUT)") (class "Default")
      (node (ref "IC1") (pin "8") (pinfunction "OUT_8") (pintype "output"))
      (node (ref "R21") (pin "1") (pinfunction "1_1") (pintype "passive"))
      (node (ref "R43") (pin "2") (pinfunction "2_2") (pintype "passive"))
    )
    (net (code "33") (name "Net-(IC1D--IN)") (class "Default")
      (node (ref "IC1") (pin "13") (pinfunction "-IN_13") (pintype "input"))
      (node (ref "R20") (pin "1") (pinfunction "1_1") (pintype "passive"))
      (node (ref "R21") (pin "2") (pinfunction "2_2") (pintype "passive"))
      (node (ref "R22") (pin "2") (pinfunction "2_2") (pintype "passive"))
    )
    (net (code "34") (name "Net-(IC2A--IN)") (class "Default")
      (node (ref "IC2") (pin "1") (pinfunction "OUT_1") (pintype "output"))
      (node (ref "IC2") (pin "2") (pinfunction "-IN_2") (pintype "input"))
    )
    (net (code "35") (name "Net-(IC2B--IN)") (class "Default")
      (node (ref "IC2") (pin "6") (pinfunction "-IN_6") (pintype "input"))
      (node (ref "IC6") (pin "12") (pinfunction "OUT_12") (pintype "output"))
      (node (ref "R64") (pin "1") (pinfunction "1_1") (pintype "passive"))
    )
    (net (code "36") (name "Net-(IC2C--IN)") (class "Default")
      (node (ref "IC2") (pin "9") (pinfunction "-IN_9") (pintype "input"))
      (node (ref "IC6") (pin "5") (pinfunction "OUT_5") (pintype "output"))
      (node (ref "R35") (pin "1") (pinfunction "1_1") (pintype "passive"))
    )
    (net (code "37") (name "Net-(IC2D--IN)") (class "Default")
      (node (ref "IC2") (pin "13") (pinfunction "-IN_13") (pintype "input"))
      (node (ref "IC2") (pin "14") (pinfunction "OUT_14") (pintype "output"))
    )
    (net (code "38") (name "Net-(IC3A--IN)") (class "Default")
      (node (ref "IC3") (pin "2") (pinfunction "-IN_2") (pintype "input"))
      (node (ref "R17") (pin "2") (pinfunction "2_2") (pintype "passive"))
      (node (ref "R33") (pin "1") (pinfunction "1_1") (pintype "passive"))
      (node (ref "R34") (pin "2") (pinfunction "2_2") (pintype "passive"))
    )
    (net (code "39") (name "Net-(IC3A-OUT)") (class "Default")
      (node (ref "IC3") (pin "1") (pinfunction "OUT_1") (pintype "output"))
      (node (ref "R31") (pin "1") (pinfunction "1_1") (pintype "passive"))
      (node (ref "R33") (pin "2") (pinfunction "2_2") (pintype "passive"))
    )
    (net (code "40") (name "Net-(IC3B--IN)") (class "Default")
      (node (ref "IC3") (pin "6") (pinfunction "-IN_6") (pintype "input"))
      (node (ref "R50") (pin "2") (pinfunction "2_2") (pintype "passive"))
      (node (ref "R51") (pin "2") (pinfunction "2_2") (pintype "passive"))
      (node (ref "R52") (pin "1") (pinfunction "1_1") (pintype "passive"))
    )
    (net (code "41") (name "Net-(IC3C--IN)") (class "Default")
      (node (ref "IC3") (pin "9") (pinfunction "-IN_9") (pintype "input"))
      (node (ref "R57") (pin "2") (pinfunction "2_2") (pintype "passive"))
      (node (ref "R58") (pin "1") (pinfunction "1_1") (pintype "passive"))
      (node (ref "R59") (pin "2") (pinfunction "2_2") (pintype "passive"))
    )
    (net (code "42") (name "Net-(IC3D--IN)") (class "Default")
      (node (ref "IC3") (pin "13") (pinfunction "-IN_13") (pintype "input"))
      (node (ref "R18") (pin "2") (pinfunction "2_2") (pintype "passive"))
      (node (ref "R38") (pin "1") (pinfunction "1_1") (pintype "passive"))
      (node (ref "R39") (pin "2") (pinfunction "2_2") (pintype "passive"))
    )
    (net (code "43") (name "Net-(IC3D-OUT)") (class "Default")
      (node (ref "IC3") (pin "14") (pinfunction "OUT_14") (pintype "output"))
      (node (ref "R32") (pin "1") (pinfunction "1_1") (pintype "passive"))
      (node (ref "R38") (pin "2") (pinfunction "2_2") (pintype "passive"))
    )
    (net (code "44") (name "Net-(IC4A--IN)") (class "Default")
      (node (ref "C17") (pin "1") (pinfunction "1_1") (pintype "passive"))
      (node (ref "IC4") (pin "2") (pinfunction "-IN_2") (pintype "input"))
      (node (ref "Q2") (pin "6") (pinfunction "C_6") (pintype "passive"))
      (node (ref "R68") (pin "2") (pinfunction "2_2") (pintype "passive"))
    )
    (net (code "45") (name "Net-(IC4A-OUT)") (class "Default")
      (node (ref "C17") (pin "2") (pinfunction "2_2") (pintype "passive"))
      (node (ref "IC4") (pin "1") (pinfunction "OUT_1") (pintype "output"))
      (node (ref "R70") (pin "1") (pinfunction "1_1") (pintype "passive"))
    )
    (net (code "46") (name "Net-(IC4B--IN)") (class "Default")
      (node (ref "IC4") (pin "6") (pinfunction "-IN_6") (pintype "input"))
      (node (ref "R60") (pin "2") (pinfunction "2_2") (pintype "passive"))
      (node (ref "R61") (pin "2") (pinfunction "2_2") (pintype "passive"))
      (node (ref "R62") (pin "1") (pinfunction "1_1") (pintype "passive"))
    )
    (net (code "47") (name "Net-(IC4C--IN)") (class "Default")
      (node (ref "IC4") (pin "9") (pinfunction "-IN_9") (pintype "input"))
      (node (ref "R53") (pin "1") (pinfunction "1_1") (pintype "passive"))
      (node (ref "R54") (pin "2") (pinfunction "2_2") (pintype "passive"))
      (node (ref "R63") (pin "2") (pinfunction "2_2") (pintype "passive"))
    )
    (net (code "48") (name "Net-(IC4D--IN)") (class "Default")
      (node (ref "C18") (pin "1") (pinfunction "1_1") (pintype "passive"))
      (node (ref "IC4") (pin "13") (pinfunction "-IN_13") (pintype "input"))
      (node (ref "Q1") (pin "6") (pinfunction "C_6") (pintype "passive"))
      (node (ref "R69") (pin "2") (pinfunction "2_2") (pintype "passive"))
    )
    (net (code "49") (name "Net-(IC4D-OUT)") (class "Default")
      (node (ref "C18") (pin "2") (pinfunction "2_2") (pintype "passive"))
      (node (ref "IC4") (pin "14") (pinfunction "OUT_14") (pintype "output"))
      (node (ref "R71") (pin "1") (pinfunction "1_1") (pintype "passive"))
    )
    (net (code "50") (name "Net-(IC5A--IN)") (class "Default")
      (node (ref "IC5") (pin "2") (pinfunction "-IN_2") (pintype "input"))
      (node (ref "JP2") (pin "1") (pinfunction "1_1") (pintype "passive"))
      (node (ref "R14") (pin "2") (pinfunction "2_2") (pintype "passive"))
      (node (ref "R48") (pin "1") (pinfunction "1_1") (pintype "passive"))
      (node (ref "R49") (pin "2") (pinfunction "2_2") (pintype "passive"))
    )
    (net (code "51") (name "Net-(IC5A-OUT)") (class "Default")
      (node (ref "IC5") (pin "1") (pinfunction "OUT_1") (pintype "output"))
      (node (ref "R30") (pin "1") (pinfunction "1_1") (pintype "passive"))
      (node (ref "R48") (pin "2") (pinfunction "2_2") (pintype "passive"))
    )
    (net (code "52") (name "Net-(IC5B--IN)") (class "Default")
      (node (ref "IC5") (pin "6") (pinfunction "-IN_6") (pintype "input"))
      (node (ref "R16") (pin "2") (pinfunction "2_2") (pintype "passive"))
      (node (ref "R23") (pin "1") (pinfunction "1_1") (pintype "passive"))
      (node (ref "R24") (pin "2") (pinfunction "2_2") (pintype "passive"))
    )
    (net (code "53") (name "Net-(IC5C--IN)") (class "Default")
      (node (ref "IC5") (pin "9") (pinfunction "-IN_9") (pintype "input"))
      (node (ref "R65") (pin "2") (pinfunction "2_2") (pintype "passive"))
      (node (ref "R66") (pin "2") (pinfunction "2_2") (pintype "passive"))
      (node (ref "R67") (pin "1") (pinfunction "1_1") (pintype "passive"))
    )
    (net (code "54") (name "Net-(IC5D--IN)") (class "Default")
      (node (ref "IC5") (pin "13") (pinfunction "-IN_13") (pintype "input"))
      (node (ref "JP1") (pin "1") (pinfunction "1_1") (pintype "passive"))
      (node (ref "R12") (pin "2") (pinfunction "2_2") (pintype "passive"))
      (node (ref "R44") (pin "1") (pinfunction "1_1") (pintype "passive"))
      (node (ref "R47") (pin "2") (pinfunction "2_2") (pintype "passive"))
    )
    (net (code "55") (name "Net-(IC5D-OUT)") (class "Default")
      (node (ref "IC5") (pin "14") (pinfunction "OUT_14") (pintype "output"))
      (node (ref "R29") (pin "1") (pinfunction "1_1") (pintype "passive"))
      (node (ref "R44") (pin "2") (pinfunction "2_2") (pintype "passive"))
    )
    (net (code "56") (name "Net-(IC6A-+IN)") (class "Default")
      (node (ref "IC6") (pin "3") (pinfunction "+IN_3") (pintype "input"))
      (node (ref "R37") (pin "2") (pinfunction "2_2") (pintype "passive"))
      (node (ref "R6") (pin "2") (pinfunction "2_2") (pintype "passive"))
    )
    (net (code "57") (name "Net-(IC6A--IN)") (class "Default")
      (node (ref "IC6") (pin "4") (pinfunction "-IN_4") (pintype "input"))
      (node (ref "R5") (pin "2") (pinfunction "2_2") (pintype "passive"))
    )
    (net (code "58") (name "Net-(IC6A-DIODE{slash}BIAS)") (class "Default")
      (node (ref "IC6") (pin "2") (pinfunction "DIODE/BIAS_2") (pintype "passive"))
      (node (ref "R25") (pin "2") (pinfunction "2_2") (pintype "passive"))
    )
    (net (code "59") (name "Net-(IC6B-+IN)") (class "Default")
      (node (ref "IC6") (pin "14") (pinfunction "+IN_14") (pintype "input"))
      (node (ref "R7") (pin "2") (pinfunction "2_2") (pintype "passive"))
    )
    (net (code "60") (name "Net-(IC6B--IN)") (class "Default")
      (node (ref "IC6") (pin "13") (pinfunction "-IN_13") (pintype "input"))
      (node (ref "R36") (pin "2") (pinfunction "2_2") (pintype "passive"))
      (node (ref "R8") (pin "2") (pinfunction "2_2") (pintype "passive"))
    )
    (net (code "61") (name "Net-(IC6B-DIODE{slash}BIAS)") (class "Default")
      (node (ref "IC6") (pin "15") (pinfunction "DIODE/BIAS_15") (pintype "passive"))
      (node (ref "R26") (pin "2") (pinfunction "2_2") (pintype "passive"))
    )
    (net (code "62") (name "Net-(IC7A-+IN)") (class "Default")
      (node (ref "IC7") (pin "3") (pinfunction "+IN_3") (pintype "input"))
      (node (ref "R1") (pin "2") (pinfunction "2_2") (pintype "passive"))
      (node (ref "R46") (pin "2") (pinfunction "2_2") (pintype "passive"))
    )
    (net (code "63") (name "Net-(IC7A--IN)") (class "Default")
      (node (ref "IC7") (pin "4") (pinfunction "-IN_4") (pintype "input"))
      (node (ref "R2") (pin "2") (pinfunction "2_2") (pintype "passive"))
    )
    (net (code "64") (name "Net-(IC7A-DIODE{slash}BIAS)") (class "Default")
      (node (ref "IC7") (pin "2") (pinfunction "DIODE/BIAS_2") (pintype "passive"))
      (node (ref "R27") (pin "2") (pinfunction "2_2") (pintype "passive"))
    )
    (net (code "65") (name "Net-(IC7B-+IN)") (class "Default")
      (node (ref "IC7") (pin "14") (pinfunction "+IN_14") (pintype "input"))
      (node (ref "R3") (pin "2") (pinfunction "2_2") (pintype "passive"))
    )
    (net (code "66") (name "Net-(IC7B--IN)") (class "Default")
      (node (ref "IC7") (pin "13") (pinfunction "-IN_13") (pintype "input"))
      (node (ref "R4") (pin "2") (pinfunction "2_2") (pintype "passive"))
      (node (ref "R45") (pin "2") (pinfunction "2_2") (pintype "passive"))
    )
    (net (code "67") (name "Net-(IC7B-DIODE{slash}BIAS)") (class "Default")
      (node (ref "IC7") (pin "15") (pinfunction "DIODE/BIAS_15") (pintype "passive"))
      (node (ref "R28") (pin "2") (pinfunction "2_2") (pintype "passive"))
    )
    (net (code "68") (name "Net-(JP1-Pad2)") (class "Default")
      (node (ref "JP1") (pin "2") (pinfunction "2_2") (pintype "passive"))
      (node (ref "R13") (pin "2") (pinfunction "2_2") (pintype "passive"))
    )
    (net (code "69") (name "Net-(JP2-Pad2)") (class "Default")
      (node (ref "JP2") (pin "2") (pinfunction "2_2") (pintype "passive"))
      (node (ref "R15") (pin "2") (pinfunction "2_2") (pintype "passive"))
    )
    (net (code "70") (name "Net-(Q1A-B)") (class "Default")
      (node (ref "Q1") (pin "2") (pinfunction "B_2") (pintype "passive"))
      (node (ref "R10") (pin "1") (pinfunction "1_1") (pintype "passive"))
      (node (ref "R41") (pin "2") (pinfunction "2_2") (pintype "passive"))
    )
    (net (code "71") (name "Net-(Q1A-E)") (class "Default")
      (node (ref "Q1") (pin "1") (pinfunction "E_1") (pintype "passive"))
      (node (ref "Q1") (pin "4") (pinfunction "E_4") (pintype "passive"))
      (node (ref "R71") (pin "2") (pinfunction "2_2") (pintype "passive"))
    )
    (net (code "72") (name "Net-(Q2A-B)") (class "Default")
      (node (ref "Q2") (pin "2") (pinfunction "B_2") (pintype "passive"))
      (node (ref "R40") (pin "2") (pinfunction "2_2") (pintype "passive"))
      (node (ref "R9") (pin "1") (pinfunction "1_1") (pintype "passive"))
    )
    (net (code "73") (name "Net-(Q2A-E)") (class "Default")
      (node (ref "Q2") (pin "1") (pinfunction "E_1") (pintype "passive"))
      (node (ref "Q2") (pin "4") (pinfunction "E_4") (pintype "passive"))
      (node (ref "R70") (pin "2") (pinfunction "2_2") (pintype "passive"))
    )
    (net (code "74") (name "Net-(Q4-PadS)") (class "Default")
      (node (ref "Q4") (pin "S") (pinfunction "S_S") (pintype "passive"))
      (node (ref "R11") (pin "2") (pinfunction "2_2") (pintype "passive"))
    )
    (net (code "75") (name "Net-(RV1-S)") (class "Default")
      (node (ref "R60") (pin "1") (pinfunction "1_1") (pintype "passive"))
      (node (ref "RV1") (pin "2") (pinfunction "S_2") (pintype "passive"))
    )
    (net (code "76") (name "Net-(RV2-S)") (class "Default")
      (node (ref "R63") (pin "1") (pinfunction "1_1") (pintype "passive"))
      (node (ref "RV2") (pin "2") (pinfunction "S_2") (pintype "passive"))
    )
    (net (code "77") (name "Net-(RV3-S)") (class "Default")
      (node (ref "R50") (pin "1") (pinfunction "1_1") (pintype "passive"))
      (node (ref "RV3") (pin "2") (pinfunction "S_2") (pintype "passive"))
    )
    (net (code "78") (name "Net-(RV4-S)") (class "Default")
      (node (ref "R57") (pin "1") (pinfunction "1_1") (pintype "passive"))
      (node (ref "RV4") (pin "2") (pinfunction "S_2") (pintype "passive"))
    )
    (net (code "79") (name "Net-(RV5-S)") (class "Default")
      (node (ref "R65") (pin "1") (pinfunction "1_1") (pintype "passive"))
      (node (ref "RV5") (pin "2") (pinfunction "S_2") (pintype "passive"))
    )
    (net (code "80") (name "VAC_A_CV") (class "Default")
      (node (ref "IC4") (pin "7") (pinfunction "OUT_7") (pintype "output"))
      (node (ref "R40") (pin "1") (pinfunction "1_1") (pintype "passive"))
      (node (ref "R62") (pin "2") (pinfunction "2_2") (pintype "passive"))
    )
    (net (code "81") (name "VAC_A_CV_IN") (class "Default")
      (node (ref "R61") (pin "1") (pinfunction "1_1") (pintype "passive"))
      (node (ref "X1") (pin "2") (pinfunction "1_2") (pintype "passive"))
    )
    (net (code "82") (name "VAC_B_CV") (class "Default")
      (node (ref "IC4") (pin "8") (pinfunction "OUT_8") (pintype "output"))
      (node (ref "R41") (pin "1") (pinfunction "1_1") (pintype "passive"))
      (node (ref "R53") (pin "2") (pinfunction "2_2") (pintype "passive"))
    )
    (net (code "83") (name "VAC_B_CV_IN") (class "Default")
      (node (ref "R54") (pin "1") (pinfunction "1_1") (pintype "passive"))
      (node (ref "X1") (pin "3") (pinfunction "1_3") (pintype "passive"))
    )
    (net (code "84") (name "WET") (class "Default")
      (node (ref "C21") (pin "2") (pinfunction "2_2") (pintype "passive"))
      (node (ref "R37") (pin "1") (pinfunction "1_1") (pintype "passive"))
      (node (ref "R46") (pin "1") (pinfunction "1_1") (pintype "passive"))
      (node (ref "TP4") (pin "TP") (pinfunction "TP_TP") (pintype "input"))
    )
    (net (code "85") (name "unconnected-(IC6A-BUFF{slash}OUT-Pad8)") (class "Default")
      (node (ref "IC6") (pin "8") (pinfunction "BUFF/OUT_8") (pintype "output"))
    )
    (net (code "86") (name "unconnected-(IC6B-BUFF{slash}OUT-Pad9)") (class "Default")
      (node (ref "IC6") (pin "9") (pinfunction "BUFF/OUT_9") (pintype "output"))
    )
    (net (code "87") (name "unconnected-(IC7A-BUFF{slash}OUT-Pad8)") (class "Default")
      (node (ref "IC7") (pin "8") (pinfunction "BUFF/OUT_8") (pintype "output"))
    )
    (net (code "88") (name "unconnected-(IC7B-BUFF{slash}OUT-Pad9)") (class "Default")
      (node (ref "IC7") (pin "9") (pinfunction "BUFF/OUT_9") (pintype "output"))
    )
    (net (code "89") (name "unconnected-(SV1-Pad11)") (class "Default")
      (node (ref "SV1") (pin "11") (pinfunction "11_11") (pintype "passive"))
    )
    (net (code "90") (name "unconnected-(SV1-Pad12)") (class "Default")
      (node (ref "SV1") (pin "12") (pinfunction "12_12") (pintype "passive"))
    )
    (net (code "91") (name "unconnected-(SV1-Pad13)") (class "Default")
      (node (ref "SV1") (pin "13") (pinfunction "13_13") (pintype "passive"))
    )
    (net (code "92") (name "unconnected-(SV1-Pad14)") (class "Default")
      (node (ref "SV1") (pin "14") (pinfunction "14_14") (pintype "passive"))
    )
    (net (code "93") (name "unconnected-(SV1-Pad15)") (class "Default")
      (node (ref "SV1") (pin "15") (pinfunction "15_15") (pintype "passive"))
    )
    (net (code "94") (name "unconnected-(SV1-Pad16)") (class "Default")
      (node (ref "SV1") (pin "16") (pinfunction "16_16") (pintype "passive"))
    )
  )
)
